# arpie_main.net
KiCad netlist of a schematic drawn in EAGLE
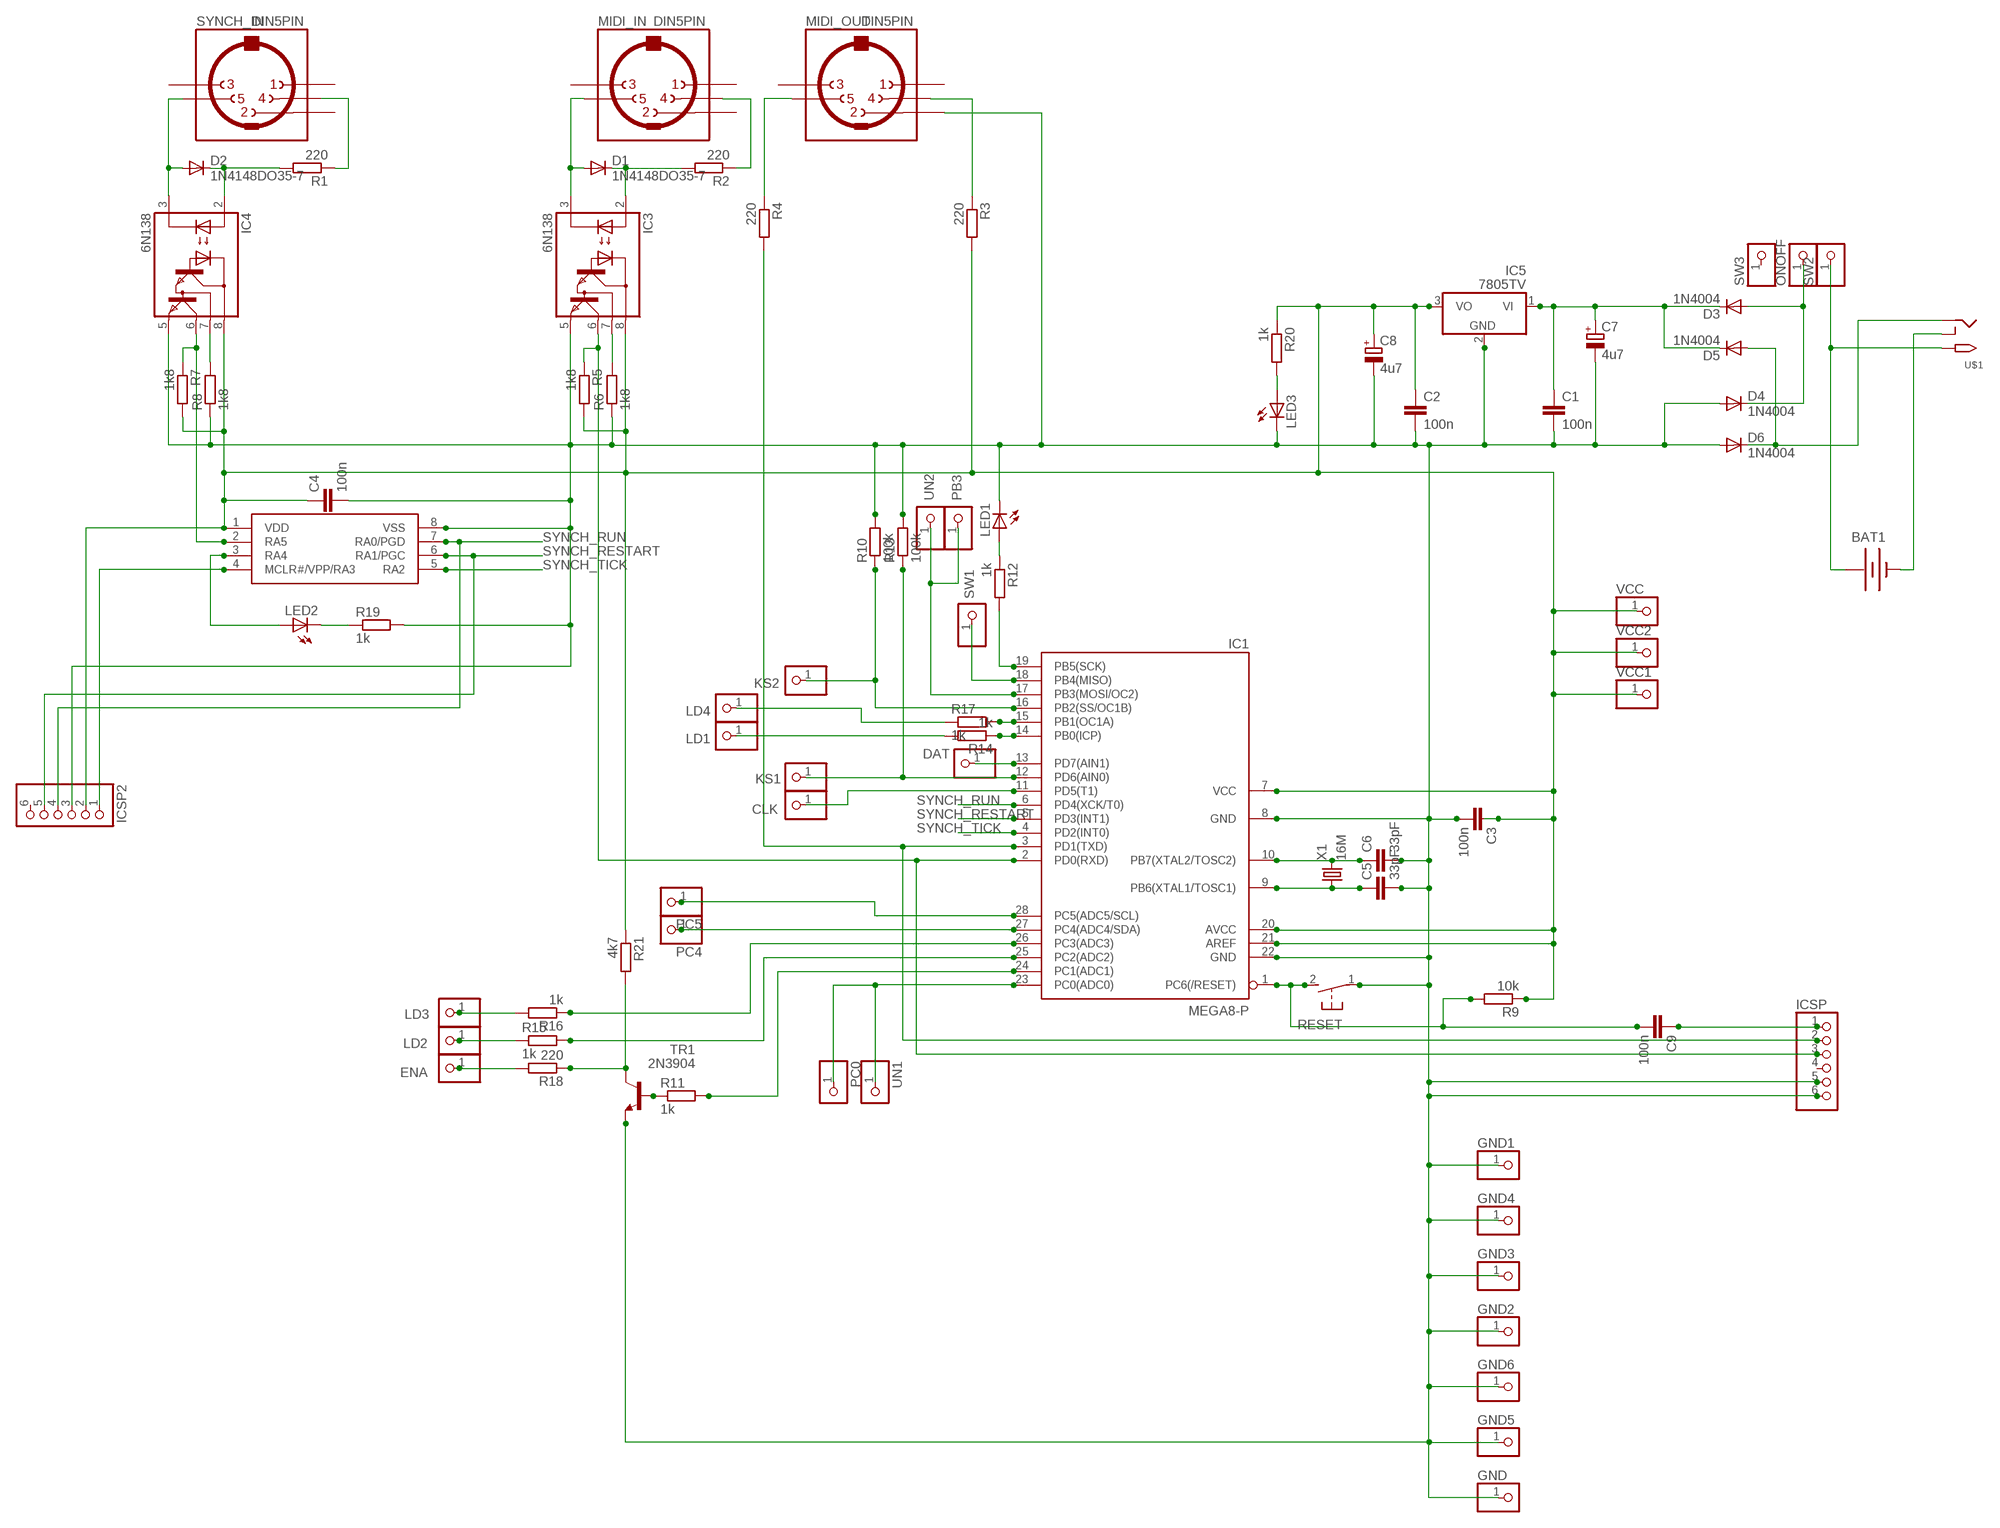
[diagram p0: schematic, sheet 1]

(export (version "E")
  (design (tool "Eeschema 10.0.6"))
  (components
    (comp (ref "BAT1")
      (value "BATTERY")
      (footprint "eagle-import:PP3_BATTERBOX")
      (libsource (lib "eagle-import") (part "BATTERY"))
    )
    (comp (ref "C1")
      (value "100n")
      (footprint "eagle-import:C025-024X044")
      (libsource (lib "eagle-import") (part "C-EU025-024X044"))
    )
    (comp (ref "C2")
      (value "100n")
      (footprint "eagle-import:C025-024X044")
      (libsource (lib "eagle-import") (part "C-EU025-024X044"))
    )
    (comp (ref "C3")
      (value "100n")
      (footprint "eagle-import:C025-024X044")
      (libsource (lib "eagle-import") (part "C-EU025-024X044"))
    )
    (comp (ref "C4")
      (value "100n")
      (footprint "eagle-import:C025-024X044")
      (libsource (lib "eagle-import") (part "C-EU025-024X044"))
    )
    (comp (ref "C5")
      (value "33pF")
      (footprint "eagle-import:C025-024X044")
      (libsource (lib "eagle-import") (part "C-EU025-024X044"))
    )
    (comp (ref "C6")
      (value "33pF")
      (footprint "eagle-import:C025-024X044")
      (libsource (lib "eagle-import") (part "C-EU025-024X044"))
    )
    (comp (ref "C7")
      (value "4u7")
      (footprint "eagle-import:E2,5-7")
      (libsource (lib "eagle-import") (part "CPOL-EUE2.5-7"))
    )
    (comp (ref "C8")
      (value "4u7")
      (footprint "eagle-import:E2,5-7")
      (libsource (lib "eagle-import") (part "CPOL-EUE2.5-7"))
    )
    (comp (ref "C9")
      (value "100n")
      (footprint "eagle-import:C025-024X044")
      (libsource (lib "eagle-import") (part "C-EU025-024X044"))
    )
    (comp (ref "CLK")
      (value "PINHD-1X1")
      (footprint "eagle-import:1X01")
      (libsource (lib "eagle-import") (part "PINHD-1X1"))
    )
    (comp (ref "D1")
      (value "1N4148DO35-7")
      (footprint "eagle-import:DO35-7")
      (libsource (lib "eagle-import") (part "1N4148DO35-7"))
    )
    (comp (ref "D2")
      (value "1N4148DO35-7")
      (footprint "eagle-import:DO35-7")
      (libsource (lib "eagle-import") (part "1N4148DO35-7"))
    )
    (comp (ref "D3")
      (value "1N4004")
      (footprint "eagle-import:DO-VERT")
      (libsource (lib "eagle-import") (part "1N4004"))
    )
    (comp (ref "D4")
      (value "1N4004")
      (footprint "eagle-import:DO-VERT")
      (libsource (lib "eagle-import") (part "1N4004"))
    )
    (comp (ref "D5")
      (value "1N4004")
      (footprint "eagle-import:DO-VERT")
      (libsource (lib "eagle-import") (part "1N4004"))
    )
    (comp (ref "D6")
      (value "1N4004")
      (footprint "eagle-import:DO-VERT")
      (libsource (lib "eagle-import") (part "1N4004"))
    )
    (comp (ref "DAT")
      (value "PINHD-1X1")
      (footprint "eagle-import:1X01")
      (libsource (lib "eagle-import") (part "PINHD-1X1"))
    )
    (comp (ref "ENA")
      (value "PINHD-1X1")
      (footprint "eagle-import:1X01")
      (libsource (lib "eagle-import") (part "PINHD-1X1"))
    )
    (comp (ref "GND")
      (value "PINHD-1X1")
      (footprint "eagle-import:1X01")
      (libsource (lib "eagle-import") (part "PINHD-1X1"))
    )
    (comp (ref "GND1")
      (value "PINHD-1X1")
      (footprint "eagle-import:1X01")
      (libsource (lib "eagle-import") (part "PINHD-1X1"))
    )
    (comp (ref "GND2")
      (value "PINHD-1X1")
      (footprint "eagle-import:1X01")
      (libsource (lib "eagle-import") (part "PINHD-1X1"))
    )
    (comp (ref "GND3")
      (value "PINHD-1X1")
      (footprint "eagle-import:1X01")
      (libsource (lib "eagle-import") (part "PINHD-1X1"))
    )
    (comp (ref "GND4")
      (value "PINHD-1X1")
      (footprint "eagle-import:1X01")
      (libsource (lib "eagle-import") (part "PINHD-1X1"))
    )
    (comp (ref "GND5")
      (value "PINHD-1X1")
      (footprint "eagle-import:1X01")
      (libsource (lib "eagle-import") (part "PINHD-1X1"))
    )
    (comp (ref "GND6")
      (value "PINHD-1X1")
      (footprint "eagle-import:1X01")
      (libsource (lib "eagle-import") (part "PINHD-1X1"))
    )
    (comp (ref "IC1")
      (value "MEGA8-P")
      (footprint "eagle-import:DIL28-3")
      (libsource (lib "eagle-import") (part "MEGA8-P"))
    )
    (comp (ref "IC2")
      (value "PIC12F1822")
      (footprint "eagle-import:DIL08")
      (libsource (lib "eagle-import") (part "PIC12F1822"))
    )
    (comp (ref "IC3")
      (value "6N138")
      (footprint "eagle-import:DIL08")
      (libsource (lib "eagle-import") (part "6N138"))
    )
    (comp (ref "IC4")
      (value "6N138")
      (footprint "eagle-import:DIL08")
      (libsource (lib "eagle-import") (part "6N138"))
    )
    (comp (ref "IC5")
      (value "7805TV")
      (footprint "eagle-import:TO220V")
      (libsource (lib "eagle-import") (part "78TV05"))
    )
    (comp (ref "ICSP")
      (value "PINHD-1X6")
      (footprint "eagle-import:1X06")
      (libsource (lib "eagle-import") (part "PINHD-1X6"))
    )
    (comp (ref "ICSP2")
      (value "PINHD-1X6")
      (footprint "eagle-import:1X06")
      (libsource (lib "eagle-import") (part "PINHD-1X6"))
    )
    (comp (ref "KS1")
      (value "PINHD-1X1")
      (footprint "eagle-import:1X01")
      (libsource (lib "eagle-import") (part "PINHD-1X1"))
    )
    (comp (ref "KS2")
      (value "PINHD-1X1")
      (footprint "eagle-import:1X01")
      (libsource (lib "eagle-import") (part "PINHD-1X1"))
    )
    (comp (ref "LD1")
      (value "PINHD-1X1")
      (footprint "eagle-import:1X01")
      (libsource (lib "eagle-import") (part "PINHD-1X1"))
    )
    (comp (ref "LD2")
      (value "PINHD-1X1")
      (footprint "eagle-import:1X01")
      (libsource (lib "eagle-import") (part "PINHD-1X1"))
    )
    (comp (ref "LD3")
      (value "PINHD-1X1")
      (footprint "eagle-import:1X01")
      (libsource (lib "eagle-import") (part "PINHD-1X1"))
    )
    (comp (ref "LD4")
      (value "PINHD-1X1")
      (footprint "eagle-import:1X01")
      (libsource (lib "eagle-import") (part "PINHD-1X1"))
    )
    (comp (ref "LED1")
      (value "LED3MM")
      (footprint "eagle-import:LED3MM")
      (libsource (lib "eagle-import") (part "LED3MM"))
    )
    (comp (ref "LED2")
      (value "LED3MM")
      (footprint "eagle-import:LED3MM")
      (libsource (lib "eagle-import") (part "LED3MM"))
    )
    (comp (ref "LED3")
      (value "LED3MM")
      (footprint "eagle-import:LED3MM")
      (libsource (lib "eagle-import") (part "LED3MM"))
    )
    (comp (ref "MIDI_IN")
      (value "DIN5PIN")
      (footprint "eagle-import:RAPIDDIN5")
      (libsource (lib "eagle-import") (part "DIN5PINRAPIDDIN5"))
    )
    (comp (ref "MIDI_OUT")
      (value "DIN5PIN")
      (footprint "eagle-import:RAPIDDIN5")
      (libsource (lib "eagle-import") (part "DIN5PINRAPIDDIN5"))
    )
    (comp (ref "ONOFF")
      (value "PINHD-1X1")
      (footprint "eagle-import:1X01")
      (libsource (lib "eagle-import") (part "PINHD-1X1"))
    )
    (comp (ref "PB3")
      (value "PINHD-1X1")
      (footprint "eagle-import:1X01")
      (libsource (lib "eagle-import") (part "PINHD-1X1"))
    )
    (comp (ref "PC0")
      (value "PINHD-1X1")
      (footprint "eagle-import:1X01")
      (libsource (lib "eagle-import") (part "PINHD-1X1"))
    )
    (comp (ref "PC4")
      (value "PINHD-1X1")
      (footprint "eagle-import:1X01")
      (libsource (lib "eagle-import") (part "PINHD-1X1"))
    )
    (comp (ref "PC5")
      (value "PINHD-1X1")
      (footprint "eagle-import:1X01")
      (libsource (lib "eagle-import") (part "PINHD-1X1"))
    )
    (comp (ref "R1")
      (value "220")
      (footprint "eagle-import:0207_7")
      (libsource (lib "eagle-import") (part "R-EU_0207/7"))
    )
    (comp (ref "R2")
      (value "220")
      (footprint "eagle-import:0207_7")
      (libsource (lib "eagle-import") (part "R-EU_0207/7"))
    )
    (comp (ref "R3")
      (value "220")
      (footprint "eagle-import:0207_7")
      (libsource (lib "eagle-import") (part "R-EU_0207/7"))
    )
    (comp (ref "R4")
      (value "220")
      (footprint "eagle-import:0207_7")
      (libsource (lib "eagle-import") (part "R-EU_0207/7"))
    )
    (comp (ref "R5")
      (value "1k8")
      (footprint "eagle-import:0207_7")
      (libsource (lib "eagle-import") (part "R-EU_0207/7"))
    )
    (comp (ref "R6")
      (value "1k8")
      (footprint "eagle-import:0207_7")
      (libsource (lib "eagle-import") (part "R-EU_0207/7"))
    )
    (comp (ref "R7")
      (value "1k8")
      (footprint "eagle-import:0207_7")
      (libsource (lib "eagle-import") (part "R-EU_0207/7"))
    )
    (comp (ref "R8")
      (value "1k8")
      (footprint "eagle-import:0207_7")
      (libsource (lib "eagle-import") (part "R-EU_0207/7"))
    )
    (comp (ref "R9")
      (value "10k")
      (footprint "eagle-import:0207_7")
      (libsource (lib "eagle-import") (part "R-EU_0207/7"))
    )
    (comp (ref "R10")
      (value "100k")
      (footprint "eagle-import:0207_7")
      (libsource (lib "eagle-import") (part "R-EU_0207/7"))
    )
    (comp (ref "R11")
      (value "1k")
      (footprint "eagle-import:0207_7")
      (libsource (lib "eagle-import") (part "R-EU_0207/7"))
    )
    (comp (ref "R12")
      (value "1k")
      (footprint "eagle-import:0207_7")
      (libsource (lib "eagle-import") (part "R-EU_0207/7"))
    )
    (comp (ref "R13")
      (value "100k")
      (footprint "eagle-import:0207_2V")
      (libsource (lib "eagle-import") (part "R-EU_0207/2V"))
    )
    (comp (ref "R14")
      (value "1k")
      (footprint "eagle-import:0207_2V")
      (libsource (lib "eagle-import") (part "R-EU_0207/2V"))
    )
    (comp (ref "R15")
      (value "1k")
      (footprint "eagle-import:0207_2V")
      (libsource (lib "eagle-import") (part "R-EU_0207/2V"))
    )
    (comp (ref "R16")
      (value "1k")
      (footprint "eagle-import:0207_2V")
      (libsource (lib "eagle-import") (part "R-EU_0207/2V"))
    )
    (comp (ref "R17")
      (value "1k")
      (footprint "eagle-import:0207_2V")
      (libsource (lib "eagle-import") (part "R-EU_0207/2V"))
    )
    (comp (ref "R18")
      (value "220")
      (footprint "eagle-import:0207_2V")
      (libsource (lib "eagle-import") (part "R-EU_0207/2V"))
    )
    (comp (ref "R19")
      (value "1k")
      (footprint "eagle-import:0207_7")
      (libsource (lib "eagle-import") (part "R-EU_0207/7"))
    )
    (comp (ref "R20")
      (value "1k")
      (footprint "eagle-import:0207_7")
      (libsource (lib "eagle-import") (part "R-EU_0207/7"))
    )
    (comp (ref "R21")
      (value "4k7")
      (footprint "eagle-import:0207_2V")
      (libsource (lib "eagle-import") (part "R-EU_0207/2V"))
    )
    (comp (ref "RESET")
      (value "31-XX")
      (footprint "eagle-import:B3F-31XX")
      (libsource (lib "eagle-import") (part "31-XX"))
    )
    (comp (ref "SW1")
      (value "PINHD-1X1")
      (footprint "eagle-import:1X01")
      (libsource (lib "eagle-import") (part "PINHD-1X1"))
    )
    (comp (ref "SW2")
      (value "PINHD-1X1")
      (footprint "eagle-import:1X01")
      (libsource (lib "eagle-import") (part "PINHD-1X1"))
    )
    (comp (ref "SW3")
      (value "PINHD-1X1")
      (footprint "eagle-import:1X01")
      (libsource (lib "eagle-import") (part "PINHD-1X1"))
    )
    (comp (ref "SYNCH_IN")
      (value "DIN5PIN")
      (footprint "eagle-import:RAPIDDIN5")
      (libsource (lib "eagle-import") (part "DIN5PINRAPIDDIN5"))
    )
    (comp (ref "TR1")
      (value "2N3904")
      (footprint "eagle-import:TO92")
      (libsource (lib "eagle-import") (part "2N3904"))
    )
    (comp (ref "U$1")
      (value "2.1MMJACKTHM")
      (footprint "eagle-import:PJ-102A")
      (libsource (lib "eagle-import") (part "2.1MMJACKTHM"))
    )
    (comp (ref "UN1")
      (value "PINHD-1X1")
      (footprint "eagle-import:1X01")
      (libsource (lib "eagle-import") (part "PINHD-1X1"))
    )
    (comp (ref "UN2")
      (value "PINHD-1X1")
      (footprint "eagle-import:1X01")
      (libsource (lib "eagle-import") (part "PINHD-1X1"))
    )
    (comp (ref "VCC")
      (value "PINHD-1X1")
      (footprint "eagle-import:1X01")
      (libsource (lib "eagle-import") (part "PINHD-1X1"))
    )
    (comp (ref "VCC1")
      (value "PINHD-1X1")
      (footprint "eagle-import:1X01")
      (libsource (lib "eagle-import") (part "PINHD-1X1"))
    )
    (comp (ref "VCC2")
      (value "PINHD-1X1")
      (footprint "eagle-import:1X01")
      (libsource (lib "eagle-import") (part "PINHD-1X1"))
    )
    (comp (ref "X1")
      (value "16M")
      (footprint "eagle-import:HC49_S")
      (libsource (lib "eagle-import") (part "CRYSTALHC49S"))
    )
  )
  (nets
    (net (code "1") (name "/SYNCH_RESTART") (class "Default")
      (node (ref "IC1") (pin "5") (pinfunction "PD3(INT1)_5") (pintype "bidirectional"))
      (node (ref "IC2") (pin "6") (pinfunction "RA1/PGC_6") (pintype "bidirectional"))
      (node (ref "ICSP2") (pin "5") (pinfunction "5_5") (pintype "passive"))
    )
    (net (code "2") (name "/SYNCH_RUN") (class "Default")
      (node (ref "IC1") (pin "6") (pinfunction "PD4(XCK/T0)_6") (pintype "bidirectional"))
      (node (ref "IC2") (pin "7") (pinfunction "RA0/PGD_7") (pintype "bidirectional"))
      (node (ref "ICSP2") (pin "4") (pinfunction "4_4") (pintype "passive"))
    )
    (net (code "3") (name "/SYNCH_TICK") (class "Default")
      (node (ref "IC1") (pin "4") (pinfunction "PD2(INT0)_4") (pintype "bidirectional"))
      (node (ref "IC2") (pin "5") (pinfunction "RA2_5") (pintype "bidirectional"))
    )
    (net (code "4") (name "Net-(BAT1-+)") (class "Default")
      (node (ref "BAT1") (pin "9V") (pinfunction "+_9V") (pintype "power_in"))
      (node (ref "SW2") (pin "1") (pinfunction "1_1") (pintype "passive"))
      (node (ref "U$1") (pin "TIP") (pinfunction "TIP_TIP") (pintype "bidirectional"))
    )
    (net (code "5") (name "Net-(BAT1--)") (class "Default")
      (node (ref "BAT1") (pin "0V") (pinfunction "-_0V") (pintype "power_in"))
      (node (ref "U$1") (pin "RING_SW") (pinfunction "RING_SW_RING_SW") (pintype "bidirectional"))
    )
    (net (code "6") (name "Net-(C9-Pad1)") (class "Default")
      (node (ref "C9") (pin "1") (pinfunction "1_1") (pintype "passive"))
      (node (ref "ICSP") (pin "1") (pinfunction "1_1") (pintype "passive"))
    )
    (net (code "7") (name "Net-(D3-PadA)") (class "Default")
      (node (ref "D3") (pin "A") (pinfunction "A_A") (pintype "passive"))
      (node (ref "D4") (pin "C") (pinfunction "C_C") (pintype "passive"))
      (node (ref "ONOFF") (pin "1") (pinfunction "1_1") (pintype "passive"))
    )
    (net (code "8") (name "Net-(D5-PadA)") (class "Default")
      (node (ref "D5") (pin "A") (pinfunction "A_A") (pintype "passive"))
      (node (ref "D6") (pin "C") (pinfunction "C_C") (pintype "passive"))
      (node (ref "U$1") (pin "RING") (pinfunction "RING_RING") (pintype "bidirectional"))
    )
    (net (code "9") (name "Net-(ENA-Pad1)") (class "Default")
      (node (ref "ENA") (pin "1") (pinfunction "1_1") (pintype "passive"))
      (node (ref "R18") (pin "2") (pinfunction "2_2") (pintype "passive"))
    )
    (net (code "10") (name "Net-(IC1-AREF)") (class "Default")
      (node (ref "C2") (pin "1") (pinfunction "1_1") (pintype "passive"))
      (node (ref "C3") (pin "1") (pinfunction "1_1") (pintype "passive"))
      (node (ref "C4") (pin "1") (pinfunction "1_1") (pintype "passive"))
      (node (ref "C8") (pin "+") (pinfunction "+_+") (pintype "passive"))
      (node (ref "IC1") (pin "20") (pinfunction "AVCC_20") (pintype "power_in"))
      (node (ref "IC1") (pin "21") (pinfunction "AREF_21") (pintype "passive"))
      (node (ref "IC1") (pin "7") (pinfunction "VCC_7") (pintype "power_in"))
      (node (ref "IC2") (pin "1") (pinfunction "VDD_1") (pintype "power_in"))
      (node (ref "IC3") (pin "8") (pinfunction "VCC_8") (pintype "passive"))
      (node (ref "IC4") (pin "8") (pinfunction "VCC_8") (pintype "passive"))
      (node (ref "IC5") (pin "3") (pinfunction "VO_3") (pintype "passive"))
      (node (ref "ICSP2") (pin "2") (pinfunction "2_2") (pintype "passive"))
      (node (ref "R20") (pin "1") (pinfunction "1_1") (pintype "passive"))
      (node (ref "R21") (pin "1") (pinfunction "1_1") (pintype "passive"))
      (node (ref "R3") (pin "2") (pinfunction "2_2") (pintype "passive"))
      (node (ref "R5") (pin "2") (pinfunction "2_2") (pintype "passive"))
      (node (ref "R7") (pin "2") (pinfunction "2_2") (pintype "passive"))
      (node (ref "R9") (pin "1") (pinfunction "1_1") (pintype "passive"))
      (node (ref "VCC") (pin "1") (pinfunction "1_1") (pintype "passive"))
      (node (ref "VCC1") (pin "1") (pinfunction "1_1") (pintype "passive"))
      (node (ref "VCC2") (pin "1") (pinfunction "1_1") (pintype "passive"))
    )
    (net (code "11") (name "Net-(IC1-PB0(ICP))") (class "Default")
      (node (ref "IC1") (pin "14") (pinfunction "PB0(ICP)_14") (pintype "bidirectional"))
      (node (ref "R14") (pin "1") (pinfunction "1_1") (pintype "passive"))
    )
    (net (code "12") (name "Net-(IC1-PB1(OC1A))") (class "Default")
      (node (ref "IC1") (pin "15") (pinfunction "PB1(OC1A)_15") (pintype "bidirectional"))
      (node (ref "R17") (pin "2") (pinfunction "2_2") (pintype "passive"))
    )
    (net (code "13") (name "Net-(IC1-PB2(SS{slash}OC1B))") (class "Default")
      (node (ref "IC1") (pin "16") (pinfunction "PB2(SS/OC1B)_16") (pintype "bidirectional"))
      (node (ref "KS2") (pin "1") (pinfunction "1_1") (pintype "passive"))
      (node (ref "R10") (pin "1") (pinfunction "1_1") (pintype "passive"))
    )
    (net (code "14") (name "Net-(IC1-PB3(MOSI{slash}OC2))") (class "Default")
      (node (ref "IC1") (pin "17") (pinfunction "PB3(MOSI/OC2)_17") (pintype "bidirectional"))
      (node (ref "PB3") (pin "1") (pinfunction "1_1") (pintype "passive"))
      (node (ref "UN2") (pin "1") (pinfunction "1_1") (pintype "passive"))
    )
    (net (code "15") (name "Net-(IC1-PB4(MISO))") (class "Default")
      (node (ref "IC1") (pin "18") (pinfunction "PB4(MISO)_18") (pintype "bidirectional"))
      (node (ref "SW1") (pin "1") (pinfunction "1_1") (pintype "passive"))
    )
    (net (code "16") (name "Net-(IC1-PB5(SCK))") (class "Default")
      (node (ref "IC1") (pin "19") (pinfunction "PB5(SCK)_19") (pintype "bidirectional"))
      (node (ref "R12") (pin "2") (pinfunction "2_2") (pintype "passive"))
    )
    (net (code "17") (name "Net-(IC1-PB6(XTAL1{slash}TOSC1))") (class "Default")
      (node (ref "C5") (pin "1") (pinfunction "1_1") (pintype "passive"))
      (node (ref "IC1") (pin "9") (pinfunction "PB6(XTAL1/TOSC1)_9") (pintype "bidirectional"))
      (node (ref "X1") (pin "1") (pinfunction "1_1") (pintype "passive"))
    )
    (net (code "18") (name "Net-(IC1-PB7(XTAL2{slash}TOSC2))") (class "Default")
      (node (ref "C6") (pin "1") (pinfunction "1_1") (pintype "passive"))
      (node (ref "IC1") (pin "10") (pinfunction "PB7(XTAL2/TOSC2)_10") (pintype "bidirectional"))
      (node (ref "X1") (pin "2") (pinfunction "2_2") (pintype "passive"))
    )
    (net (code "19") (name "Net-(IC1-PC0(ADC0))") (class "Default")
      (node (ref "IC1") (pin "23") (pinfunction "PC0(ADC0)_23") (pintype "bidirectional"))
      (node (ref "PC0") (pin "1") (pinfunction "1_1") (pintype "passive"))
      (node (ref "UN1") (pin "1") (pinfunction "1_1") (pintype "passive"))
    )
    (net (code "20") (name "Net-(IC1-PC1(ADC1))") (class "Default")
      (node (ref "IC1") (pin "24") (pinfunction "PC1(ADC1)_24") (pintype "bidirectional"))
      (node (ref "R11") (pin "2") (pinfunction "2_2") (pintype "passive"))
    )
    (net (code "21") (name "Net-(IC1-PC2(ADC2))") (class "Default")
      (node (ref "IC1") (pin "25") (pinfunction "PC2(ADC2)_25") (pintype "bidirectional"))
      (node (ref "R15") (pin "2") (pinfunction "2_2") (pintype "passive"))
    )
    (net (code "22") (name "Net-(IC1-PC3(ADC3))") (class "Default")
      (node (ref "IC1") (pin "26") (pinfunction "PC3(ADC3)_26") (pintype "bidirectional"))
      (node (ref "R16") (pin "1") (pinfunction "1_1") (pintype "passive"))
    )
    (net (code "23") (name "Net-(IC1-PC4(ADC4{slash}SDA))") (class "Default")
      (node (ref "IC1") (pin "27") (pinfunction "PC4(ADC4/SDA)_27") (pintype "bidirectional"))
      (node (ref "PC4") (pin "1") (pinfunction "1_1") (pintype "passive"))
    )
    (net (code "24") (name "Net-(IC1-PC5(ADC5{slash}SCL))") (class "Default")
      (node (ref "IC1") (pin "28") (pinfunction "PC5(ADC5/SCL)_28") (pintype "bidirectional"))
      (node (ref "PC5") (pin "1") (pinfunction "1_1") (pintype "passive"))
    )
    (net (code "25") (name "Net-(IC1-PC6({slash}RESET))") (class "Default")
      (node (ref "C9") (pin "2") (pinfunction "2_2") (pintype "passive"))
      (node (ref "IC1") (pin "1") (pinfunction "PC6(/RESET)_1") (pintype "bidirectional"))
      (node (ref "R9") (pin "2") (pinfunction "2_2") (pintype "passive"))
      (node (ref "RESET") (pin "2") (pinfunction "S_2") (pintype "passive"))
    )
    (net (code "26") (name "Net-(IC1-PD0(RXD))") (class "Default")
      (node (ref "IC1") (pin "2") (pinfunction "PD0(RXD)_2") (pintype "bidirectional"))
      (node (ref "IC3") (pin "6") (pinfunction "VO_6") (pintype "passive"))
      (node (ref "ICSP") (pin "3") (pinfunction "3_3") (pintype "passive"))
      (node (ref "R5") (pin "1") (pinfunction "1_1") (pintype "passive"))
    )
    (net (code "27") (name "Net-(IC1-PD1(TXD))") (class "Default")
      (node (ref "IC1") (pin "3") (pinfunction "PD1(TXD)_3") (pintype "bidirectional"))
      (node (ref "ICSP") (pin "2") (pinfunction "2_2") (pintype "passive"))
      (node (ref "R4") (pin "2") (pinfunction "2_2") (pintype "passive"))
    )
    (net (code "28") (name "Net-(IC1-PD5(T1))") (class "Default")
      (node (ref "CLK") (pin "1") (pinfunction "1_1") (pintype "passive"))
      (node (ref "IC1") (pin "11") (pinfunction "PD5(T1)_11") (pintype "bidirectional"))
    )
    (net (code "29") (name "Net-(IC1-PD6(AIN0))") (class "Default")
      (node (ref "IC1") (pin "12") (pinfunction "PD6(AIN0)_12") (pintype "bidirectional"))
      (node (ref "KS1") (pin "1") (pinfunction "1_1") (pintype "passive"))
      (node (ref "R13") (pin "1") (pinfunction "1_1") (pintype "passive"))
    )
    (net (code "30") (name "Net-(IC1-PD7(AIN1))") (class "Default")
      (node (ref "DAT") (pin "1") (pinfunction "1_1") (pintype "passive"))
      (node (ref "IC1") (pin "13") (pinfunction "PD7(AIN1)_13") (pintype "bidirectional"))
    )
    (net (code "31") (name "Net-(IC2-MCLR#{slash}VPP{slash}RA3)") (class "Default")
      (node (ref "IC2") (pin "4") (pinfunction "MCLR#/VPP/RA3_4") (pintype "bidirectional"))
      (node (ref "ICSP2") (pin "1") (pinfunction "1_1") (pintype "passive"))
    )
    (net (code "32") (name "Net-(IC2-RA4)") (class "Default")
      (node (ref "IC2") (pin "3") (pinfunction "RA4_3") (pintype "bidirectional"))
      (node (ref "LED2") (pin "A") (pinfunction "A_A") (pintype "passive"))
    )
    (net (code "33") (name "Net-(IC2-RA5)") (class "Default")
      (node (ref "IC2") (pin "2") (pinfunction "RA5_2") (pintype "bidirectional"))
      (node (ref "IC4") (pin "6") (pinfunction "VO_6") (pintype "passive"))
      (node (ref "R7") (pin "1") (pinfunction "1_1") (pintype "passive"))
    )
    (net (code "34") (name "Net-(IC2-VSS)") (class "Default")
      (node (ref "C1") (pin "2") (pinfunction "2_2") (pintype "passive"))
      (node (ref "C2") (pin "2") (pinfunction "2_2") (pintype "passive"))
      (node (ref "C3") (pin "2") (pinfunction "2_2") (pintype "passive"))
      (node (ref "C4") (pin "2") (pinfunction "2_2") (pintype "passive"))
      (node (ref "C5") (pin "2") (pinfunction "2_2") (pintype "passive"))
      (node (ref "C6") (pin "2") (pinfunction "2_2") (pintype "passive"))
      (node (ref "C7") (pin "-") (pinfunction "-_-") (pintype "passive"))
      (node (ref "C8") (pin "-") (pinfunction "-_-") (pintype "passive"))
      (node (ref "D4") (pin "A") (pinfunction "A_A") (pintype "passive"))
      (node (ref "D6") (pin "A") (pinfunction "A_A") (pintype "passive"))
      (node (ref "GND") (pin "1") (pinfunction "1_1") (pintype "passive"))
      (node (ref "GND1") (pin "1") (pinfunction "1_1") (pintype "passive"))
      (node (ref "GND2") (pin "1") (pinfunction "1_1") (pintype "passive"))
      (node (ref "GND3") (pin "1") (pinfunction "1_1") (pintype "passive"))
      (node (ref "GND4") (pin "1") (pinfunction "1_1") (pintype "passive"))
      (node (ref "GND5") (pin "1") (pinfunction "1_1") (pintype "passive"))
      (node (ref "GND6") (pin "1") (pinfunction "1_1") (pintype "passive"))
      (node (ref "IC1") (pin "22") (pinfunction "GND_22") (pintype "power_in"))
      (node (ref "IC1") (pin "8") (pinfunction "GND_8") (pintype "power_in"))
      (node (ref "IC2") (pin "8") (pinfunction "VSS_8") (pintype "power_in"))
      (node (ref "IC3") (pin "5") (pinfunction "GND_5") (pintype "passive"))
      (node (ref "IC4") (pin "5") (pinfunction "GND_5") (pintype "passive"))
      (node (ref "IC5") (pin "2") (pinfunction "GND_2") (pintype "passive"))
      (node (ref "ICSP") (pin "5") (pinfunction "5_5") (pintype "passive"))
      (node (ref "ICSP") (pin "6") (pinfunction "6_6") (pintype "passive"))
      (node (ref "ICSP2") (pin "3") (pinfunction "3_3") (pintype "passive"))
      (node (ref "LED1") (pin "K") (pinfunction "C_K") (pintype "passive"))
      (node (ref "LED3") (pin "K") (pinfunction "C_K") (pintype "passive"))
      (node (ref "MIDI_OUT") (pin "2") (pinfunction "2_2") (pintype "passive"))
      (node (ref "R10") (pin "2") (pinfunction "2_2") (pintype "passive"))
      (node (ref "R13") (pin "2") (pinfunction "2_2") (pintype "passive"))
      (node (ref "R19") (pin "2") (pinfunction "2_2") (pintype "passive"))
      (node (ref "R6") (pin "1") (pinfunction "1_1") (pintype "passive"))
      (node (ref "R8") (pin "1") (pinfunction "1_1") (pintype "passive"))
      (node (ref "RESET") (pin "1") (pinfunction "P_1") (pintype "passive"))
      (node (ref "TR1") (pin "3") (pinfunction "E_3") (pintype "passive"))
    )
    (net (code "35") (name "Net-(IC3-A)") (class "Default")
      (node (ref "D1") (pin "C") (pinfunction "C_C") (pintype "passive"))
      (node (ref "IC3") (pin "2") (pinfunction "A_2") (pintype "passive"))
      (node (ref "R2") (pin "2") (pinfunction "2_2") (pintype "passive"))
    )
    (net (code "36") (name "Net-(IC3-C)") (class "Default")
      (node (ref "D1") (pin "A") (pinfunction "A_A") (pintype "passive"))
      (node (ref "IC3") (pin "3") (pinfunction "C_3") (pintype "passive"))
      (node (ref "MIDI_IN") (pin "5") (pinfunction "5_5") (pintype "passive"))
    )
    (net (code "37") (name "Net-(IC3-VB)") (class "Default")
      (node (ref "IC3") (pin "7") (pinfunction "VB_7") (pintype "passive"))
      (node (ref "R6") (pin "2") (pinfunction "2_2") (pintype "passive"))
    )
    (net (code "38") (name "Net-(IC4-A)") (class "Default")
      (node (ref "D2") (pin "C") (pinfunction "C_C") (pintype "passive"))
      (node (ref "IC4") (pin "2") (pinfunction "A_2") (pintype "passive"))
      (node (ref "R1") (pin "2") (pinfunction "2_2") (pintype "passive"))
    )
    (net (code "39") (name "Net-(IC4-C)") (class "Default")
      (node (ref "D2") (pin "A") (pinfunction "A_A") (pintype "passive"))
      (node (ref "IC4") (pin "3") (pinfunction "C_3") (pintype "passive"))
      (node (ref "SYNCH_IN") (pin "5") (pinfunction "5_5") (pintype "passive"))
    )
    (net (code "40") (name "Net-(IC4-VB)") (class "Default")
      (node (ref "IC4") (pin "7") (pinfunction "VB_7") (pintype "passive"))
      (node (ref "R8") (pin "2") (pinfunction "2_2") (pintype "passive"))
    )
    (net (code "41") (name "Net-(IC5-VI)") (class "Default")
      (node (ref "C1") (pin "1") (pinfunction "1_1") (pintype "passive"))
      (node (ref "C7") (pin "+") (pinfunction "+_+") (pintype "passive"))
      (node (ref "D3") (pin "C") (pinfunction "C_C") (pintype "passive"))
      (node (ref "D5") (pin "C") (pinfunction "C_C") (pintype "passive"))
      (node (ref "IC5") (pin "1") (pinfunction "VI_1") (pintype "input"))
    )
    (net (code "42") (name "Net-(LD1-Pad1)") (class "Default")
      (node (ref "LD1") (pin "1") (pinfunction "1_1") (pintype "passive"))
      (node (ref "R14") (pin "2") (pinfunction "2_2") (pintype "passive"))
    )
    (net (code "43") (name "Net-(LD2-Pad1)") (class "Default")
      (node (ref "LD2") (pin "1") (pinfunction "1_1") (pintype "passive"))
      (node (ref "R15") (pin "1") (pinfunction "1_1") (pintype "passive"))
    )
    (net (code "44") (name "Net-(LD3-Pad1)") (class "Default")
      (node (ref "LD3") (pin "1") (pinfunction "1_1") (pintype "passive"))
      (node (ref "R16") (pin "2") (pinfunction "2_2") (pintype "passive"))
    )
    (net (code "45") (name "Net-(LD4-Pad1)") (class "Default")
      (node (ref "LD4") (pin "1") (pinfunction "1_1") (pintype "passive"))
      (node (ref "R17") (pin "1") (pinfunction "1_1") (pintype "passive"))
    )
    (net (code "46") (name "Net-(LED1-PadA)") (class "Default")
      (node (ref "LED1") (pin "A") (pinfunction "A_A") (pintype "passive"))
      (node (ref "R12") (pin "1") (pinfunction "1_1") (pintype "passive"))
    )
    (net (code "47") (name "Net-(LED2-C)") (class "Default")
      (node (ref "LED2") (pin "K") (pinfunction "C_K") (pintype "passive"))
      (node (ref "R19") (pin "1") (pinfunction "1_1") (pintype "passive"))
    )
    (net (code "48") (name "Net-(LED3-PadA)") (class "Default")
      (node (ref "LED3") (pin "A") (pinfunction "A_A") (pintype "passive"))
      (node (ref "R20") (pin "2") (pinfunction "2_2") (pintype "passive"))
    )
    (net (code "49") (name "Net-(MIDI_IN-Pad4)") (class "Default")
      (node (ref "MIDI_IN") (pin "4") (pinfunction "4_4") (pintype "passive"))
      (node (ref "R2") (pin "1") (pinfunction "1_1") (pintype "passive"))
    )
    (net (code "50") (name "Net-(MIDI_OUT-Pad4)") (class "Default")
      (node (ref "MIDI_OUT") (pin "4") (pinfunction "4_4") (pintype "passive"))
      (node (ref "R3") (pin "1") (pinfunction "1_1") (pintype "passive"))
    )
    (net (code "51") (name "Net-(MIDI_OUT-Pad5)") (class "Default")
      (node (ref "MIDI_OUT") (pin "5") (pinfunction "5_5") (pintype "passive"))
      (node (ref "R4") (pin "1") (pinfunction "1_1") (pintype "passive"))
    )
    (net (code "52") (name "Net-(R1-Pad1)") (class "Default")
      (node (ref "R1") (pin "1") (pinfunction "1_1") (pintype "passive"))
      (node (ref "SYNCH_IN") (pin "4") (pinfunction "4_4") (pintype "passive"))
    )
    (net (code "53") (name "Net-(TR1-B)") (class "Default")
      (node (ref "R11") (pin "1") (pinfunction "1_1") (pintype "passive"))
      (node (ref "TR1") (pin "2") (pinfunction "B_2") (pintype "passive"))
    )
    (net (code "54") (name "Net-(TR1-C)") (class "Default")
      (node (ref "R18") (pin "1") (pinfunction "1_1") (pintype "passive"))
      (node (ref "R21") (pin "2") (pinfunction "2_2") (pintype "passive"))
      (node (ref "TR1") (pin "1") (pinfunction "C_1") (pintype "passive"))
    )
    (net (code "55") (name "unconnected-(ICSP-Pad4)") (class "Default")
      (node (ref "ICSP") (pin "4") (pinfunction "4_4") (pintype "passive"))
    )
    (net (code "56") (name "unconnected-(ICSP2-Pad6)") (class "Default")
      (node (ref "ICSP2") (pin "6") (pinfunction "6_6") (pintype "passive"))
    )
    (net (code "57") (name "unconnected-(MIDI_IN-Pad1)") (class "Default")
      (node (ref "MIDI_IN") (pin "1") (pinfunction "1_1") (pintype "passive"))
    )
    (net (code "58") (name "unconnected-(MIDI_IN-Pad2)") (class "Default")
      (node (ref "MIDI_IN") (pin "2") (pinfunction "2_2") (pintype "passive"))
    )
    (net (code "59") (name "unconnected-(MIDI_IN-Pad3)") (class "Default")
      (node (ref "MIDI_IN") (pin "3") (pinfunction "3_3") (pintype "passive"))
    )
    (net (code "60") (name "unconnected-(MIDI_OUT-Pad1)") (class "Default")
      (node (ref "MIDI_OUT") (pin "1") (pinfunction "1_1") (pintype "passive"))
    )
    (net (code "61") (name "unconnected-(MIDI_OUT-Pad3)") (class "Default")
      (node (ref "MIDI_OUT") (pin "3") (pinfunction "3_3") (pintype "passive"))
    )
    (net (code "62") (name "unconnected-(SW3-Pad1)") (class "Default")
      (node (ref "SW3") (pin "1") (pinfunction "1_1") (pintype "passive"))
    )
    (net (code "63") (name "unconnected-(SYNCH_IN-Pad1)") (class "Default")
      (node (ref "SYNCH_IN") (pin "1") (pinfunction "1_1") (pintype "passive"))
    )
    (net (code "64") (name "unconnected-(SYNCH_IN-Pad2)") (class "Default")
      (node (ref "SYNCH_IN") (pin "2") (pinfunction "2_2") (pintype "passive"))
    )
    (net (code "65") (name "unconnected-(SYNCH_IN-Pad3)") (class "Default")
      (node (ref "SYNCH_IN") (pin "3") (pinfunction "3_3") (pintype "passive"))
    )
  )
)
